# 16_Bit_Register.net
KiCad netlist of a schematic drawn in EAGLE
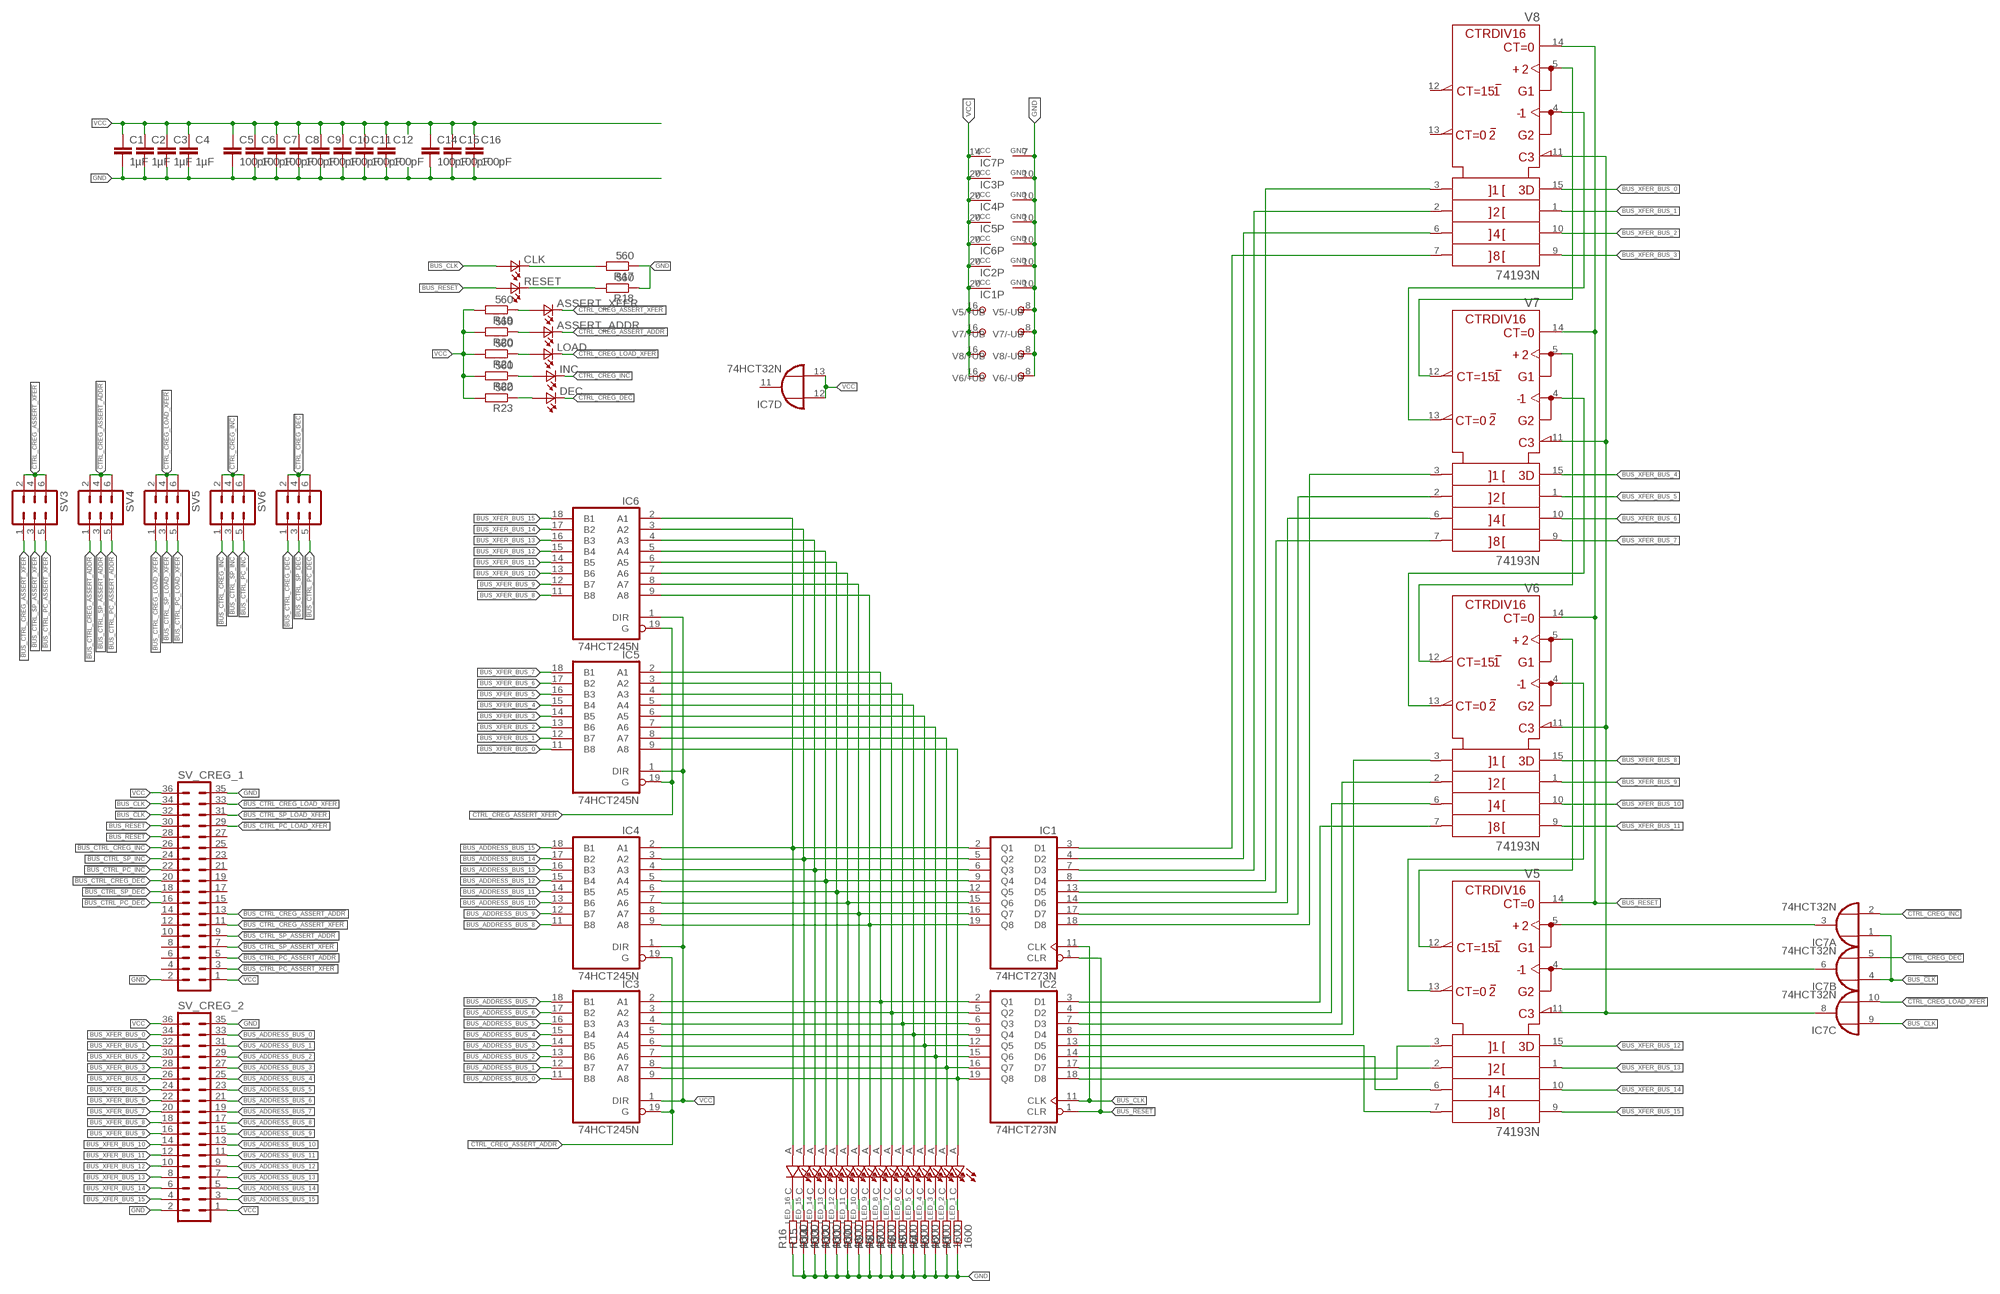
[diagram p0: schematic, sheet 1]

(export (version "E")
  (design (tool "Eeschema 10.0.6"))
  (components
    (comp (ref "ASSERT_ADDR")
      (value "LTST-C193TBKT-5A")
      (footprint "eagle-import:0603")
      (libsource (lib "eagle-import") (part "LTST-C193TBKT-5A"))
    )
    (comp (ref "ASSERT_XFER")
      (value "LTST-C193TBKT-5A")
      (footprint "eagle-import:0603")
      (libsource (lib "eagle-import") (part "LTST-C193TBKT-5A"))
    )
    (comp (ref "C1")
      (value "1µF")
      (footprint "eagle-import:C0805")
      (libsource (lib "eagle-import") (part "C-EUC0805"))
    )
    (comp (ref "C2")
      (value "1µF")
      (footprint "eagle-import:C0805")
      (libsource (lib "eagle-import") (part "C-EUC0805"))
    )
    (comp (ref "C3")
      (value "1µF")
      (footprint "eagle-import:C0805")
      (libsource (lib "eagle-import") (part "C-EUC0805"))
    )
    (comp (ref "C4")
      (value "1µF")
      (footprint "eagle-import:C0805")
      (libsource (lib "eagle-import") (part "C-EUC0805"))
    )
    (comp (ref "C5")
      (value "100pF")
      (footprint "eagle-import:C0805")
      (libsource (lib "eagle-import") (part "C-EUC0805"))
    )
    (comp (ref "C6")
      (value "100pF")
      (footprint "eagle-import:C0805")
      (libsource (lib "eagle-import") (part "C-EUC0805"))
    )
    (comp (ref "C7")
      (value "100pF")
      (footprint "eagle-import:C0805")
      (libsource (lib "eagle-import") (part "C-EUC0805"))
    )
    (comp (ref "C8")
      (value "100pF")
      (footprint "eagle-import:C0805")
      (libsource (lib "eagle-import") (part "C-EUC0805"))
    )
    (comp (ref "C9")
      (value "100pF")
      (footprint "eagle-import:C0805")
      (libsource (lib "eagle-import") (part "C-EUC0805"))
    )
    (comp (ref "C10")
      (value "100pF")
      (footprint "eagle-import:C0805")
      (libsource (lib "eagle-import") (part "C-EUC0805"))
    )
    (comp (ref "C11")
      (value "100pF")
      (footprint "eagle-import:C0805")
      (libsource (lib "eagle-import") (part "C-EUC0805"))
    )
    (comp (ref "C12")
      (value "100pF")
      (footprint "eagle-import:C0805")
      (libsource (lib "eagle-import") (part "C-EUC0805"))
    )
    (comp (ref "C14")
      (value "100pF")
      (footprint "eagle-import:C0805")
      (libsource (lib "eagle-import") (part "C-EUC0805"))
    )
    (comp (ref "C15")
      (value "100pF")
      (footprint "eagle-import:C0805")
      (libsource (lib "eagle-import") (part "C-EUC0805"))
    )
    (comp (ref "C16")
      (value "100pF")
      (footprint "eagle-import:C0805")
      (libsource (lib "eagle-import") (part "C-EUC0805"))
    )
    (comp (ref "CLK")
      (value "LTST-C193TBKT-5A")
      (footprint "eagle-import:0603")
      (libsource (lib "eagle-import") (part "LTST-C193TBKT-5A"))
    )
    (comp (ref "DEC")
      (value "LTST-C193TBKT-5A")
      (footprint "eagle-import:0603")
      (libsource (lib "eagle-import") (part "LTST-C193TBKT-5A"))
    )
    (comp (ref "IC1")
      (value "74HCT273N")
      (footprint "eagle-import:DIL20")
      (libsource (lib "eagle-import") (part "74273NHCT"))
    )
    (comp (ref "IC2")
      (value "74HCT273N")
      (footprint "eagle-import:DIL20")
      (libsource (lib "eagle-import") (part "74273NHCT"))
    )
    (comp (ref "IC3")
      (value "74HCT245N")
      (footprint "eagle-import:DIL20")
      (libsource (lib "eagle-import") (part "74245NHCT"))
    )
    (comp (ref "IC4")
      (value "74HCT245N")
      (footprint "eagle-import:DIL20")
      (libsource (lib "eagle-import") (part "74245NHCT"))
    )
    (comp (ref "IC5")
      (value "74HCT245N")
      (footprint "eagle-import:DIL20")
      (libsource (lib "eagle-import") (part "74245NHCT"))
    )
    (comp (ref "IC6")
      (value "74HCT245N")
      (footprint "eagle-import:DIL20")
      (libsource (lib "eagle-import") (part "74245NHCT"))
    )
    (comp (ref "IC7")
      (value "74HCT32N")
      (footprint "eagle-import:DIL14")
      (libsource (lib "eagle-import") (part "7432NHCT"))
    )
    (comp (ref "INC")
      (value "LTST-C193TBKT-5A")
      (footprint "eagle-import:0603")
      (libsource (lib "eagle-import") (part "LTST-C193TBKT-5A"))
    )
    (comp (ref "LED_1")
      (value "LTST-C193KRKT-5A")
      (footprint "eagle-import:LEDC1608X45N")
      (fields (field (name "MANUFACTURER") "Lite-On"))
      (libsource (lib "eagle-import") (part "LTST-C193KRKT-5A"))
    )
    (comp (ref "LED_2")
      (value "LTST-C193KRKT-5A")
      (footprint "eagle-import:LEDC1608X45N")
      (fields (field (name "MANUFACTURER") "Lite-On"))
      (libsource (lib "eagle-import") (part "LTST-C193KRKT-5A"))
    )
    (comp (ref "LED_3")
      (value "LTST-C193KRKT-5A")
      (footprint "eagle-import:LEDC1608X45N")
      (fields (field (name "MANUFACTURER") "Lite-On"))
      (libsource (lib "eagle-import") (part "LTST-C193KRKT-5A"))
    )
    (comp (ref "LED_4")
      (value "LTST-C193KRKT-5A")
      (footprint "eagle-import:LEDC1608X45N")
      (fields (field (name "MANUFACTURER") "Lite-On"))
      (libsource (lib "eagle-import") (part "LTST-C193KRKT-5A"))
    )
    (comp (ref "LED_5")
      (value "LTST-C193KRKT-5A")
      (footprint "eagle-import:LEDC1608X45N")
      (fields (field (name "MANUFACTURER") "Lite-On"))
      (libsource (lib "eagle-import") (part "LTST-C193KRKT-5A"))
    )
    (comp (ref "LED_6")
      (value "LTST-C193KRKT-5A")
      (footprint "eagle-import:LEDC1608X45N")
      (fields (field (name "MANUFACTURER") "Lite-On"))
      (libsource (lib "eagle-import") (part "LTST-C193KRKT-5A"))
    )
    (comp (ref "LED_7")
      (value "LTST-C193KRKT-5A")
      (footprint "eagle-import:LEDC1608X45N")
      (fields (field (name "MANUFACTURER") "Lite-On"))
      (libsource (lib "eagle-import") (part "LTST-C193KRKT-5A"))
    )
    (comp (ref "LED_8")
      (value "LTST-C193KRKT-5A")
      (footprint "eagle-import:LEDC1608X45N")
      (fields (field (name "MANUFACTURER") "Lite-On"))
      (libsource (lib "eagle-import") (part "LTST-C193KRKT-5A"))
    )
    (comp (ref "LED_9")
      (value "LTST-C193KRKT-5A")
      (footprint "eagle-import:LEDC1608X45N")
      (fields (field (name "MANUFACTURER") "Lite-On"))
      (libsource (lib "eagle-import") (part "LTST-C193KRKT-5A"))
    )
    (comp (ref "LED_10")
      (value "LTST-C193KRKT-5A")
      (footprint "eagle-import:LEDC1608X45N")
      (fields (field (name "MANUFACTURER") "Lite-On"))
      (libsource (lib "eagle-import") (part "LTST-C193KRKT-5A"))
    )
    (comp (ref "LED_11")
      (value "LTST-C193KRKT-5A")
      (footprint "eagle-import:LEDC1608X45N")
      (fields (field (name "MANUFACTURER") "Lite-On"))
      (libsource (lib "eagle-import") (part "LTST-C193KRKT-5A"))
    )
    (comp (ref "LED_12")
      (value "LTST-C193KRKT-5A")
      (footprint "eagle-import:LEDC1608X45N")
      (fields (field (name "MANUFACTURER") "Lite-On"))
      (libsource (lib "eagle-import") (part "LTST-C193KRKT-5A"))
    )
    (comp (ref "LED_13")
      (value "LTST-C193KRKT-5A")
      (footprint "eagle-import:LEDC1608X45N")
      (fields (field (name "MANUFACTURER") "Lite-On"))
      (libsource (lib "eagle-import") (part "LTST-C193KRKT-5A"))
    )
    (comp (ref "LED_14")
      (value "LTST-C193KRKT-5A")
      (footprint "eagle-import:LEDC1608X45N")
      (fields (field (name "MANUFACTURER") "Lite-On"))
      (libsource (lib "eagle-import") (part "LTST-C193KRKT-5A"))
    )
    (comp (ref "LED_15")
      (value "LTST-C193KRKT-5A")
      (footprint "eagle-import:LEDC1608X45N")
      (fields (field (name "MANUFACTURER") "Lite-On"))
      (libsource (lib "eagle-import") (part "LTST-C193KRKT-5A"))
    )
    (comp (ref "LED_16")
      (value "LTST-C193KRKT-5A")
      (footprint "eagle-import:LEDC1608X45N")
      (fields (field (name "MANUFACTURER") "Lite-On"))
      (libsource (lib "eagle-import") (part "LTST-C193KRKT-5A"))
    )
    (comp (ref "LOAD")
      (value "LTST-C193TBKT-5A")
      (footprint "eagle-import:0603")
      (libsource (lib "eagle-import") (part "LTST-C193TBKT-5A"))
    )
    (comp (ref "R1")
      (value "1600")
      (footprint "eagle-import:R0805")
      (libsource (lib "eagle-import") (part "R-EU_R0805"))
    )
    (comp (ref "R2")
      (value "1600")
      (footprint "eagle-import:R0805")
      (libsource (lib "eagle-import") (part "R-EU_R0805"))
    )
    (comp (ref "R3")
      (value "1600")
      (footprint "eagle-import:R0805")
      (libsource (lib "eagle-import") (part "R-EU_R0805"))
    )
    (comp (ref "R4")
      (value "1600")
      (footprint "eagle-import:R0805")
      (libsource (lib "eagle-import") (part "R-EU_R0805"))
    )
    (comp (ref "R5")
      (value "1600")
      (footprint "eagle-import:R0805")
      (libsource (lib "eagle-import") (part "R-EU_R0805"))
    )
    (comp (ref "R6")
      (value "1600")
      (footprint "eagle-import:R0805")
      (libsource (lib "eagle-import") (part "R-EU_R0805"))
    )
    (comp (ref "R7")
      (value "1600")
      (footprint "eagle-import:R0805")
      (libsource (lib "eagle-import") (part "R-EU_R0805"))
    )
    (comp (ref "R8")
      (value "1600")
      (footprint "eagle-import:R0805")
      (libsource (lib "eagle-import") (part "R-EU_R0805"))
    )
    (comp (ref "R9")
      (value "1600")
      (footprint "eagle-import:R0805")
      (libsource (lib "eagle-import") (part "R-EU_R0805"))
    )
    (comp (ref "R10")
      (value "1600")
      (footprint "eagle-import:R0805")
      (libsource (lib "eagle-import") (part "R-EU_R0805"))
    )
    (comp (ref "R11")
      (value "1600")
      (footprint "eagle-import:R0805")
      (libsource (lib "eagle-import") (part "R-EU_R0805"))
    )
    (comp (ref "R12")
      (value "1600")
      (footprint "eagle-import:R0805")
      (libsource (lib "eagle-import") (part "R-EU_R0805"))
    )
    (comp (ref "R13")
      (value "1600")
      (footprint "eagle-import:R0805")
      (libsource (lib "eagle-import") (part "R-EU_R0805"))
    )
    (comp (ref "R14")
      (value "1600")
      (footprint "eagle-import:R0805")
      (libsource (lib "eagle-import") (part "R-EU_R0805"))
    )
    (comp (ref "R15")
      (value "1600")
      (footprint "eagle-import:R0805")
      (libsource (lib "eagle-import") (part "R-EU_R0805"))
    )
    (comp (ref "R16")
      (value "1600")
      (footprint "eagle-import:R0805")
      (libsource (lib "eagle-import") (part "R-EU_R0805"))
    )
    (comp (ref "R17")
      (value "560")
      (footprint "eagle-import:R0805")
      (libsource (lib "eagle-import") (part "R-EU_R0805"))
    )
    (comp (ref "R18")
      (value "560")
      (footprint "eagle-import:R0805")
      (libsource (lib "eagle-import") (part "R-EU_R0805"))
    )
    (comp (ref "R19")
      (value "560")
      (footprint "eagle-import:R0805")
      (libsource (lib "eagle-import") (part "R-EU_R0805"))
    )
    (comp (ref "R20")
      (value "560")
      (footprint "eagle-import:R0805")
      (libsource (lib "eagle-import") (part "R-EU_R0805"))
    )
    (comp (ref "R21")
      (value "560")
      (footprint "eagle-import:R0805")
      (libsource (lib "eagle-import") (part "R-EU_R0805"))
    )
    (comp (ref "R22")
      (value "560")
      (footprint "eagle-import:R0805")
      (libsource (lib "eagle-import") (part "R-EU_R0805"))
    )
    (comp (ref "R23")
      (value "560")
      (footprint "eagle-import:R0805")
      (libsource (lib "eagle-import") (part "R-EU_R0805"))
    )
    (comp (ref "RESET")
      (value "LTST-C193TBKT-5A")
      (footprint "eagle-import:0603")
      (libsource (lib "eagle-import") (part "LTST-C193TBKT-5A"))
    )
    (comp (ref "SV3")
      (value "MA03-2")
      (footprint "eagle-import:MA03-2")
      (libsource (lib "eagle-import") (part "MA03-2"))
    )
    (comp (ref "SV4")
      (value "MA03-2")
      (footprint "eagle-import:MA03-2")
      (libsource (lib "eagle-import") (part "MA03-2"))
    )
    (comp (ref "SV5")
      (value "MA03-2")
      (footprint "eagle-import:MA03-2")
      (libsource (lib "eagle-import") (part "MA03-2"))
    )
    (comp (ref "SV6")
      (value "MA03-2")
      (footprint "eagle-import:MA03-2")
      (libsource (lib "eagle-import") (part "MA03-2"))
    )
    (comp (ref "SV7")
      (value "MA03-2")
      (footprint "eagle-import:MA03-2")
      (libsource (lib "eagle-import") (part "MA03-2"))
    )
    (comp (ref "SV_CREG_1")
      (value "MA18-2")
      (footprint "eagle-import:MA18-2")
      (libsource (lib "eagle-import") (part "MA18-2"))
    )
    (comp (ref "SV_CREG_2")
      (value "MA18-2")
      (footprint "eagle-import:MA18-2")
      (libsource (lib "eagle-import") (part "MA18-2"))
    )
    (comp (ref "V5")
      (value "74193N")
      (footprint "eagle-import:DIL16")
      (libsource (lib "eagle-import") (part "74193N"))
    )
    (comp (ref "V6")
      (value "74193N")
      (footprint "eagle-import:DIL16")
      (libsource (lib "eagle-import") (part "74193N"))
    )
    (comp (ref "V7")
      (value "74193N")
      (footprint "eagle-import:DIL16")
      (libsource (lib "eagle-import") (part "74193N"))
    )
    (comp (ref "V8")
      (value "74193N")
      (footprint "eagle-import:DIL16")
      (libsource (lib "eagle-import") (part "74193N"))
    )
  )
  (nets
    (net (code "1") (name "/BUS_~{CLK}") (class "Default")
      (node (ref "IC7") (pin "1") (pinfunction "I0_1") (pintype "input"))
      (node (ref "IC7") (pin "4") (pinfunction "I0_4") (pintype "input"))
      (node (ref "SV_CREG_1") (pin "32") (pinfunction "32_32") (pintype "passive"))
    )
    (net (code "2") (name "/BUS_~{RESET}") (class "Default")
      (node (ref "IC1") (pin "1") (pinfunction "CLR_1") (pintype "input"))
      (node (ref "IC2") (pin "1") (pinfunction "CLR_1") (pintype "input"))
      (node (ref "SV_CREG_1") (pin "28") (pinfunction "28_28") (pintype "passive"))
    )
    (net (code "3") (name "/~{BUS_CTRL_CREG_ASSERT_ADDR}") (class "Default")
      (node (ref "SV4") (pin "1") (pinfunction "1_1") (pintype "passive"))
      (node (ref "SV_CREG_1") (pin "13") (pinfunction "13_13") (pintype "passive"))
    )
    (net (code "4") (name "/~{BUS_CTRL_CREG_ASSERT_XFER}") (class "Default")
      (node (ref "SV3") (pin "1") (pinfunction "1_1") (pintype "passive"))
      (node (ref "SV_CREG_1") (pin "11") (pinfunction "11_11") (pintype "passive"))
    )
    (net (code "5") (name "/~{BUS_CTRL_CREG_DEC}") (class "Default")
      (node (ref "SV7") (pin "1") (pinfunction "1_1") (pintype "passive"))
      (node (ref "SV_CREG_1") (pin "20") (pinfunction "20_20") (pintype "passive"))
    )
    (net (code "6") (name "/~{BUS_CTRL_CREG_INC}") (class "Default")
      (node (ref "SV6") (pin "1") (pinfunction "1_1") (pintype "passive"))
      (node (ref "SV_CREG_1") (pin "26") (pinfunction "26_26") (pintype "passive"))
    )
    (net (code "7") (name "/~{BUS_CTRL_CREG_LOAD_XFER}") (class "Default")
      (node (ref "SV5") (pin "1") (pinfunction "1_1") (pintype "passive"))
      (node (ref "SV_CREG_1") (pin "33") (pinfunction "33_33") (pintype "passive"))
    )
    (net (code "8") (name "/~{BUS_CTRL_PC_ASSERT_ADDR}") (class "Default")
      (node (ref "SV4") (pin "5") (pinfunction "5_5") (pintype "passive"))
      (node (ref "SV_CREG_1") (pin "5") (pinfunction "5_5") (pintype "passive"))
    )
    (net (code "9") (name "/~{BUS_CTRL_PC_ASSERT_XFER}") (class "Default")
      (node (ref "SV3") (pin "5") (pinfunction "5_5") (pintype "passive"))
      (node (ref "SV_CREG_1") (pin "3") (pinfunction "3_3") (pintype "passive"))
    )
    (net (code "10") (name "/~{BUS_CTRL_PC_DEC}") (class "Default")
      (node (ref "SV7") (pin "5") (pinfunction "5_5") (pintype "passive"))
      (node (ref "SV_CREG_1") (pin "16") (pinfunction "16_16") (pintype "passive"))
    )
    (net (code "11") (name "/~{BUS_CTRL_PC_INC}") (class "Default")
      (node (ref "SV6") (pin "5") (pinfunction "5_5") (pintype "passive"))
      (node (ref "SV_CREG_1") (pin "22") (pinfunction "22_22") (pintype "passive"))
    )
    (net (code "12") (name "/~{BUS_CTRL_PC_LOAD_XFER}") (class "Default")
      (node (ref "SV5") (pin "5") (pinfunction "5_5") (pintype "passive"))
      (node (ref "SV_CREG_1") (pin "29") (pinfunction "29_29") (pintype "passive"))
    )
    (net (code "13") (name "/~{BUS_CTRL_SP_ASSERT_ADDR}") (class "Default")
      (node (ref "SV4") (pin "3") (pinfunction "3_3") (pintype "passive"))
      (node (ref "SV_CREG_1") (pin "9") (pinfunction "9_9") (pintype "passive"))
    )
    (net (code "14") (name "/~{BUS_CTRL_SP_ASSERT_XFER}") (class "Default")
      (node (ref "SV3") (pin "3") (pinfunction "3_3") (pintype "passive"))
      (node (ref "SV_CREG_1") (pin "7") (pinfunction "7_7") (pintype "passive"))
    )
    (net (code "15") (name "/~{BUS_CTRL_SP_DEC}") (class "Default")
      (node (ref "SV7") (pin "3") (pinfunction "3_3") (pintype "passive"))
      (node (ref "SV_CREG_1") (pin "18") (pinfunction "18_18") (pintype "passive"))
    )
    (net (code "16") (name "/~{BUS_CTRL_SP_INC}") (class "Default")
      (node (ref "SV6") (pin "3") (pinfunction "3_3") (pintype "passive"))
      (node (ref "SV_CREG_1") (pin "24") (pinfunction "24_24") (pintype "passive"))
    )
    (net (code "17") (name "/~{BUS_CTRL_SP_LOAD_XFER}") (class "Default")
      (node (ref "SV5") (pin "3") (pinfunction "3_3") (pintype "passive"))
      (node (ref "SV_CREG_1") (pin "31") (pinfunction "31_31") (pintype "passive"))
    )
    (net (code "18") (name "/~{CTRL_CREG_ASSERT_ADDR}") (class "Default")
      (node (ref "ASSERT_ADDR") (pin "1") (pinfunction "K2_1") (pintype "passive"))
      (node (ref "IC3") (pin "19") (pinfunction "G_19") (pintype "input"))
      (node (ref "IC4") (pin "19") (pinfunction "G_19") (pintype "input"))
      (node (ref "SV4") (pin "2") (pinfunction "2_2") (pintype "passive"))
      (node (ref "SV4") (pin "4") (pinfunction "4_4") (pintype "passive"))
      (node (ref "SV4") (pin "6") (pinfunction "6_6") (pintype "passive"))
    )
    (net (code "19") (name "/~{CTRL_CREG_ASSERT_XFER}") (class "Default")
      (node (ref "ASSERT_XFER") (pin "1") (pinfunction "K2_1") (pintype "passive"))
      (node (ref "IC5") (pin "19") (pinfunction "G_19") (pintype "input"))
      (node (ref "IC6") (pin "19") (pinfunction "G_19") (pintype "input"))
      (node (ref "SV3") (pin "2") (pinfunction "2_2") (pintype "passive"))
      (node (ref "SV3") (pin "4") (pinfunction "4_4") (pintype "passive"))
      (node (ref "SV3") (pin "6") (pinfunction "6_6") (pintype "passive"))
    )
    (net (code "20") (name "/~{CTRL_CREG_DEC}") (class "Default")
      (node (ref "DEC") (pin "1") (pinfunction "K2_1") (pintype "passive"))
      (node (ref "IC7") (pin "5") (pinfunction "I1_5") (pintype "input"))
      (node (ref "SV7") (pin "2") (pinfunction "2_2") (pintype "passive"))
      (node (ref "SV7") (pin "4") (pinfunction "4_4") (pintype "passive"))
      (node (ref "SV7") (pin "6") (pinfunction "6_6") (pintype "passive"))
    )
    (net (code "21") (name "/~{CTRL_CREG_INC}") (class "Default")
      (node (ref "IC7") (pin "2") (pinfunction "I1_2") (pintype "input"))
      (node (ref "INC") (pin "1") (pinfunction "K2_1") (pintype "passive"))
      (node (ref "SV6") (pin "2") (pinfunction "2_2") (pintype "passive"))
      (node (ref "SV6") (pin "4") (pinfunction "4_4") (pintype "passive"))
      (node (ref "SV6") (pin "6") (pinfunction "6_6") (pintype "passive"))
    )
    (net (code "22") (name "/~{CTRL_CREG_LOAD_XFER}") (class "Default")
      (node (ref "IC7") (pin "10") (pinfunction "I1_10") (pintype "input"))
      (node (ref "LOAD") (pin "1") (pinfunction "K2_1") (pintype "passive"))
      (node (ref "SV5") (pin "2") (pinfunction "2_2") (pintype "passive"))
      (node (ref "SV5") (pin "4") (pinfunction "4_4") (pintype "passive"))
      (node (ref "SV5") (pin "6") (pinfunction "6_6") (pintype "passive"))
    )
    (net (code "23") (name "BUS_ADDRESS_BUS_0") (class "Default")
      (node (ref "IC3") (pin "11") (pinfunction "B8_11") (pintype "bidirectional"))
      (node (ref "SV_CREG_2") (pin "33") (pinfunction "33_33") (pintype "passive"))
    )
    (net (code "24") (name "BUS_ADDRESS_BUS_1") (class "Default")
      (node (ref "IC3") (pin "12") (pinfunction "B7_12") (pintype "bidirectional"))
      (node (ref "SV_CREG_2") (pin "31") (pinfunction "31_31") (pintype "passive"))
    )
    (net (code "25") (name "BUS_ADDRESS_BUS_2") (class "Default")
      (node (ref "IC3") (pin "13") (pinfunction "B6_13") (pintype "bidirectional"))
      (node (ref "SV_CREG_2") (pin "29") (pinfunction "29_29") (pintype "passive"))
    )
    (net (code "26") (name "BUS_ADDRESS_BUS_3") (class "Default")
      (node (ref "IC3") (pin "14") (pinfunction "B5_14") (pintype "bidirectional"))
      (node (ref "SV_CREG_2") (pin "27") (pinfunction "27_27") (pintype "passive"))
    )
    (net (code "27") (name "BUS_ADDRESS_BUS_4") (class "Default")
      (node (ref "IC3") (pin "15") (pinfunction "B4_15") (pintype "bidirectional"))
      (node (ref "SV_CREG_2") (pin "25") (pinfunction "25_25") (pintype "passive"))
    )
    (net (code "28") (name "BUS_ADDRESS_BUS_5") (class "Default")
      (node (ref "IC3") (pin "16") (pinfunction "B3_16") (pintype "bidirectional"))
      (node (ref "SV_CREG_2") (pin "23") (pinfunction "23_23") (pintype "passive"))
    )
    (net (code "29") (name "BUS_ADDRESS_BUS_6") (class "Default")
      (node (ref "IC3") (pin "17") (pinfunction "B2_17") (pintype "bidirectional"))
      (node (ref "SV_CREG_2") (pin "21") (pinfunction "21_21") (pintype "passive"))
    )
    (net (code "30") (name "BUS_ADDRESS_BUS_7") (class "Default")
      (node (ref "IC3") (pin "18") (pinfunction "B1_18") (pintype "bidirectional"))
      (node (ref "SV_CREG_2") (pin "19") (pinfunction "19_19") (pintype "passive"))
    )
    (net (code "31") (name "BUS_ADDRESS_BUS_8") (class "Default")
      (node (ref "IC4") (pin "11") (pinfunction "B8_11") (pintype "bidirectional"))
      (node (ref "SV_CREG_2") (pin "17") (pinfunction "17_17") (pintype "passive"))
    )
    (net (code "32") (name "BUS_ADDRESS_BUS_9") (class "Default")
      (node (ref "IC4") (pin "12") (pinfunction "B7_12") (pintype "bidirectional"))
      (node (ref "SV_CREG_2") (pin "15") (pinfunction "15_15") (pintype "passive"))
    )
    (net (code "33") (name "BUS_ADDRESS_BUS_10") (class "Default")
      (node (ref "IC4") (pin "13") (pinfunction "B6_13") (pintype "bidirectional"))
      (node (ref "SV_CREG_2") (pin "13") (pinfunction "13_13") (pintype "passive"))
    )
    (net (code "34") (name "BUS_ADDRESS_BUS_11") (class "Default")
      (node (ref "IC4") (pin "14") (pinfunction "B5_14") (pintype "bidirectional"))
      (node (ref "SV_CREG_2") (pin "11") (pinfunction "11_11") (pintype "passive"))
    )
    (net (code "35") (name "BUS_ADDRESS_BUS_12") (class "Default")
      (node (ref "IC4") (pin "15") (pinfunction "B4_15") (pintype "bidirectional"))
      (node (ref "SV_CREG_2") (pin "9") (pinfunction "9_9") (pintype "passive"))
    )
    (net (code "36") (name "BUS_ADDRESS_BUS_13") (class "Default")
      (node (ref "IC4") (pin "16") (pinfunction "B3_16") (pintype "bidirectional"))
      (node (ref "SV_CREG_2") (pin "7") (pinfunction "7_7") (pintype "passive"))
    )
    (net (code "37") (name "BUS_ADDRESS_BUS_14") (class "Default")
      (node (ref "IC4") (pin "17") (pinfunction "B2_17") (pintype "bidirectional"))
      (node (ref "SV_CREG_2") (pin "5") (pinfunction "5_5") (pintype "passive"))
    )
    (net (code "38") (name "BUS_ADDRESS_BUS_15") (class "Default")
      (node (ref "IC4") (pin "18") (pinfunction "B1_18") (pintype "bidirectional"))
      (node (ref "SV_CREG_2") (pin "3") (pinfunction "3_3") (pintype "passive"))
    )
    (net (code "39") (name "BUS_CLK") (class "Default")
      (node (ref "CLK") (pin "2") (pinfunction "A2_2") (pintype "passive"))
      (node (ref "IC1") (pin "11") (pinfunction "CLK_11") (pintype "input"))
      (node (ref "IC2") (pin "11") (pinfunction "CLK_11") (pintype "input"))
      (node (ref "IC7") (pin "9") (pinfunction "I0_9") (pintype "input"))
      (node (ref "SV_CREG_1") (pin "34") (pinfunction "34_34") (pintype "passive"))
    )
    (net (code "40") (name "BUS_RESET") (class "Default")
      (node (ref "RESET") (pin "2") (pinfunction "A2_2") (pintype "passive"))
      (node (ref "SV_CREG_1") (pin "30") (pinfunction "30_30") (pintype "passive"))
      (node (ref "V5") (pin "14") (pinfunction "CLR_14") (pintype "input"))
      (node (ref "V6") (pin "14") (pinfunction "CLR_14") (pintype "input"))
      (node (ref "V7") (pin "14") (pinfunction "CLR_14") (pintype "input"))
      (node (ref "V8") (pin "14") (pinfunction "CLR_14") (pintype "input"))
    )
    (net (code "41") (name "BUS_XFER_BUS_0") (class "Default")
      (node (ref "IC5") (pin "11") (pinfunction "B8_11") (pintype "bidirectional"))
      (node (ref "SV_CREG_2") (pin "34") (pinfunction "34_34") (pintype "passive"))
      (node (ref "V8") (pin "15") (pinfunction "A_15") (pintype "input"))
    )
    (net (code "42") (name "BUS_XFER_BUS_1") (class "Default")
      (node (ref "IC5") (pin "12") (pinfunction "B7_12") (pintype "bidirectional"))
      (node (ref "SV_CREG_2") (pin "32") (pinfunction "32_32") (pintype "passive"))
      (node (ref "V8") (pin "1") (pinfunction "B_1") (pintype "input"))
    )
    (net (code "43") (name "BUS_XFER_BUS_2") (class "Default")
      (node (ref "IC5") (pin "13") (pinfunction "B6_13") (pintype "bidirectional"))
      (node (ref "SV_CREG_2") (pin "30") (pinfunction "30_30") (pintype "passive"))
      (node (ref "V8") (pin "10") (pinfunction "C_10") (pintype "input"))
    )
    (net (code "44") (name "BUS_XFER_BUS_3") (class "Default")
      (node (ref "IC5") (pin "14") (pinfunction "B5_14") (pintype "bidirectional"))
      (node (ref "SV_CREG_2") (pin "28") (pinfunction "28_28") (pintype "passive"))
      (node (ref "V8") (pin "9") (pinfunction "D_9") (pintype "input"))
    )
    (net (code "45") (name "BUS_XFER_BUS_4") (class "Default")
      (node (ref "IC5") (pin "15") (pinfunction "B4_15") (pintype "bidirectional"))
      (node (ref "SV_CREG_2") (pin "26") (pinfunction "26_26") (pintype "passive"))
      (node (ref "V7") (pin "15") (pinfunction "A_15") (pintype "input"))
    )
    (net (code "46") (name "BUS_XFER_BUS_5") (class "Default")
      (node (ref "IC5") (pin "16") (pinfunction "B3_16") (pintype "bidirectional"))
      (node (ref "SV_CREG_2") (pin "24") (pinfunction "24_24") (pintype "passive"))
      (node (ref "V7") (pin "1") (pinfunction "B_1") (pintype "input"))
    )
    (net (code "47") (name "BUS_XFER_BUS_6") (class "Default")
      (node (ref "IC5") (pin "17") (pinfunction "B2_17") (pintype "bidirectional"))
      (node (ref "SV_CREG_2") (pin "22") (pinfunction "22_22") (pintype "passive"))
      (node (ref "V7") (pin "10") (pinfunction "C_10") (pintype "input"))
    )
    (net (code "48") (name "BUS_XFER_BUS_7") (class "Default")
      (node (ref "IC5") (pin "18") (pinfunction "B1_18") (pintype "bidirectional"))
      (node (ref "SV_CREG_2") (pin "20") (pinfunction "20_20") (pintype "passive"))
      (node (ref "V7") (pin "9") (pinfunction "D_9") (pintype "input"))
    )
    (net (code "49") (name "BUS_XFER_BUS_8") (class "Default")
      (node (ref "IC6") (pin "11") (pinfunction "B8_11") (pintype "bidirectional"))
      (node (ref "SV_CREG_2") (pin "18") (pinfunction "18_18") (pintype "passive"))
      (node (ref "V6") (pin "15") (pinfunction "A_15") (pintype "input"))
    )
    (net (code "50") (name "BUS_XFER_BUS_9") (class "Default")
      (node (ref "IC6") (pin "12") (pinfunction "B7_12") (pintype "bidirectional"))
      (node (ref "SV_CREG_2") (pin "16") (pinfunction "16_16") (pintype "passive"))
      (node (ref "V6") (pin "1") (pinfunction "B_1") (pintype "input"))
    )
    (net (code "51") (name "BUS_XFER_BUS_10") (class "Default")
      (node (ref "IC6") (pin "13") (pinfunction "B6_13") (pintype "bidirectional"))
      (node (ref "SV_CREG_2") (pin "14") (pinfunction "14_14") (pintype "passive"))
      (node (ref "V6") (pin "10") (pinfunction "C_10") (pintype "input"))
    )
    (net (code "52") (name "BUS_XFER_BUS_11") (class "Default")
      (node (ref "IC6") (pin "14") (pinfunction "B5_14") (pintype "bidirectional"))
      (node (ref "SV_CREG_2") (pin "12") (pinfunction "12_12") (pintype "passive"))
      (node (ref "V6") (pin "9") (pinfunction "D_9") (pintype "input"))
    )
    (net (code "53") (name "BUS_XFER_BUS_12") (class "Default")
      (node (ref "IC6") (pin "15") (pinfunction "B4_15") (pintype "bidirectional"))
      (node (ref "SV_CREG_2") (pin "10") (pinfunction "10_10") (pintype "passive"))
      (node (ref "V5") (pin "15") (pinfunction "A_15") (pintype "input"))
    )
    (net (code "54") (name "BUS_XFER_BUS_13") (class "Default")
      (node (ref "IC6") (pin "16") (pinfunction "B3_16") (pintype "bidirectional"))
      (node (ref "SV_CREG_2") (pin "8") (pinfunction "8_8") (pintype "passive"))
      (node (ref "V5") (pin "1") (pinfunction "B_1") (pintype "input"))
    )
    (net (code "55") (name "BUS_XFER_BUS_14") (class "Default")
      (node (ref "IC6") (pin "17") (pinfunction "B2_17") (pintype "bidirectional"))
      (node (ref "SV_CREG_2") (pin "6") (pinfunction "6_6") (pintype "passive"))
      (node (ref "V5") (pin "10") (pinfunction "C_10") (pintype "input"))
    )
    (net (code "56") (name "BUS_XFER_BUS_15") (class "Default")
      (node (ref "IC6") (pin "18") (pinfunction "B1_18") (pintype "bidirectional"))
      (node (ref "SV_CREG_2") (pin "4") (pinfunction "4_4") (pintype "passive"))
      (node (ref "V5") (pin "9") (pinfunction "D_9") (pintype "input"))
    )
    (net (code "57") (name "GND") (class "Default")
      (node (ref "C1") (pin "2") (pinfunction "2_2") (pintype "passive"))
      (node (ref "C10") (pin "2") (pinfunction "2_2") (pintype "passive"))
      (node (ref "C11") (pin "2") (pinfunction "2_2") (pintype "passive"))
      (node (ref "C12") (pin "2") (pinfunction "2_2") (pintype "passive"))
      (node (ref "C14") (pin "2") (pinfunction "2_2") (pintype "passive"))
      (node (ref "C15") (pin "2") (pinfunction "2_2") (pintype "passive"))
      (node (ref "C16") (pin "2") (pinfunction "2_2") (pintype "passive"))
      (node (ref "C2") (pin "2") (pinfunction "2_2") (pintype "passive"))
      (node (ref "C3") (pin "2") (pinfunction "2_2") (pintype "passive"))
      (node (ref "C4") (pin "2") (pinfunction "2_2") (pintype "passive"))
      (node (ref "C5") (pin "2") (pinfunction "2_2") (pintype "passive"))
      (node (ref "C6") (pin "2") (pinfunction "2_2") (pintype "passive"))
      (node (ref "C7") (pin "2") (pinfunction "2_2") (pintype "passive"))
      (node (ref "C8") (pin "2") (pinfunction "2_2") (pintype "passive"))
      (node (ref "C9") (pin "2") (pinfunction "2_2") (pintype "passive"))
      (node (ref "IC1") (pin "10") (pinfunction "GND_10") (pintype "power_in"))
      (node (ref "IC2") (pin "10") (pinfunction "GND_10") (pintype "power_in"))
      (node (ref "IC3") (pin "10") (pinfunction "GND_10") (pintype "power_in"))
      (node (ref "IC4") (pin "10") (pinfunction "GND_10") (pintype "power_in"))
      (node (ref "IC5") (pin "10") (pinfunction "GND_10") (pintype "power_in"))
      (node (ref "IC6") (pin "10") (pinfunction "GND_10") (pintype "power_in"))
      (node (ref "IC7") (pin "7") (pinfunction "GND_7") (pintype "power_in"))
      (node (ref "R1") (pin "1") (pinfunction "1_1") (pintype "passive"))
      (node (ref "R10") (pin "1") (pinfunction "1_1") (pintype "passive"))
      (node (ref "R11") (pin "1") (pinfunction "1_1") (pintype "passive"))
      (node (ref "R12") (pin "1") (pinfunction "1_1") (pintype "passive"))
      (node (ref "R13") (pin "1") (pinfunction "1_1") (pintype "passive"))
      (node (ref "R14") (pin "1") (pinfunction "1_1") (pintype "passive"))
      (node (ref "R15") (pin "1") (pinfunction "1_1") (pintype "passive"))
      (node (ref "R16") (pin "1") (pinfunction "1_1") (pintype "passive"))
      (node (ref "R17") (pin "1") (pinfunction "1_1") (pintype "passive"))
      (node (ref "R18") (pin "1") (pinfunction "1_1") (pintype "passive"))
      (node (ref "R2") (pin "1") (pinfunction "1_1") (pintype "passive"))
      (node (ref "R3") (pin "1") (pinfunction "1_1") (pintype "passive"))
      (node (ref "R4") (pin "1") (pinfunction "1_1") (pintype "passive"))
      (node (ref "R5") (pin "1") (pinfunction "1_1") (pintype "passive"))
      (node (ref "R6") (pin "1") (pinfunction "1_1") (pintype "passive"))
      (node (ref "R7") (pin "1") (pinfunction "1_1") (pintype "passive"))
      (node (ref "R8") (pin "1") (pinfunction "1_1") (pintype "passive"))
      (node (ref "R9") (pin "1") (pinfunction "1_1") (pintype "passive"))
      (node (ref "SV_CREG_1") (pin "2") (pinfunction "2_2") (pintype "passive"))
      (node (ref "SV_CREG_1") (pin "35") (pinfunction "35_35") (pintype "passive"))
      (node (ref "SV_CREG_2") (pin "2") (pinfunction "2_2") (pintype "passive"))
      (node (ref "SV_CREG_2") (pin "35") (pinfunction "35_35") (pintype "passive"))
      (node (ref "V5") (pin "8") (pinfunction "-UB_8") (pintype "power_in"))
      (node (ref "V6") (pin "8") (pinfunction "-UB_8") (pintype "power_in"))
      (node (ref "V7") (pin "8") (pinfunction "-UB_8") (pintype "power_in"))
      (node (ref "V8") (pin "8") (pinfunction "-UB_8") (pintype "power_in"))
    )
    (net (code "58") (name "Net-(ASSERT_ADDR-A2)") (class "Default")
      (node (ref "ASSERT_ADDR") (pin "2") (pinfunction "A2_2") (pintype "passive"))
      (node (ref "R20") (pin "1") (pinfunction "1_1") (pintype "passive"))
    )
    (net (code "59") (name "Net-(ASSERT_XFER-A2)") (class "Default")
      (node (ref "ASSERT_XFER") (pin "2") (pinfunction "A2_2") (pintype "passive"))
      (node (ref "R19") (pin "1") (pinfunction "1_1") (pintype "passive"))
    )
    (net (code "60") (name "Net-(CLK-K2)") (class "Default")
      (node (ref "CLK") (pin "1") (pinfunction "K2_1") (pintype "passive"))
      (node (ref "R17") (pin "2") (pinfunction "2_2") (pintype "passive"))
    )
    (net (code "61") (name "Net-(DEC-A2)") (class "Default")
      (node (ref "DEC") (pin "2") (pinfunction "A2_2") (pintype "passive"))
      (node (ref "R23") (pin "1") (pinfunction "1_1") (pintype "passive"))
    )
    (net (code "62") (name "Net-(IC1A-D1)") (class "Default")
      (node (ref "IC1") (pin "3") (pinfunction "D1_3") (pintype "input"))
      (node (ref "V8") (pin "7") (pinfunction "QD_7") (pintype "output"))
    )
    (net (code "63") (name "Net-(IC1A-D2)") (class "Default")
      (node (ref "IC1") (pin "4") (pinfunction "D2_4") (pintype "input"))
      (node (ref "V8") (pin "6") (pinfunction "QC_6") (pintype "output"))
    )
    (net (code "64") (name "Net-(IC1A-D3)") (class "Default")
      (node (ref "IC1") (pin "7") (pinfunction "D3_7") (pintype "input"))
      (node (ref "V8") (pin "2") (pinfunction "QB_2") (pintype "output"))
    )
    (net (code "65") (name "Net-(IC1A-D4)") (class "Default")
      (node (ref "IC1") (pin "8") (pinfunction "D4_8") (pintype "input"))
      (node (ref "V8") (pin "3") (pinfunction "QA_3") (pintype "output"))
    )
    (net (code "66") (name "Net-(IC1A-D5)") (class "Default")
      (node (ref "IC1") (pin "13") (pinfunction "D5_13") (pintype "input"))
      (node (ref "V7") (pin "7") (pinfunction "QD_7") (pintype "output"))
    )
    (net (code "67") (name "Net-(IC1A-D6)") (class "Default")
      (node (ref "IC1") (pin "14") (pinfunction "D6_14") (pintype "input"))
      (node (ref "V7") (pin "6") (pinfunction "QC_6") (pintype "output"))
    )
    (net (code "68") (name "Net-(IC1A-D7)") (class "Default")
      (node (ref "IC1") (pin "17") (pinfunction "D7_17") (pintype "input"))
      (node (ref "V7") (pin "2") (pinfunction "QB_2") (pintype "output"))
    )
    (net (code "69") (name "Net-(IC1A-D8)") (class "Default")
      (node (ref "IC1") (pin "18") (pinfunction "D8_18") (pintype "input"))
      (node (ref "V7") (pin "3") (pinfunction "QA_3") (pintype "output"))
    )
    (net (code "70") (name "Net-(IC1A-Q1)") (class "Default")
      (node (ref "IC1") (pin "2") (pinfunction "Q1_2") (pintype "output"))
      (node (ref "IC4") (pin "2") (pinfunction "A1_2") (pintype "bidirectional"))
      (node (ref "IC6") (pin "2") (pinfunction "A1_2") (pintype "bidirectional"))
      (node (ref "LED_16") (pin "A") (pinfunction "A_A") (pintype "passive"))
    )
    (net (code "71") (name "Net-(IC1A-Q2)") (class "Default")
      (node (ref "IC1") (pin "5") (pinfunction "Q2_5") (pintype "output"))
      (node (ref "IC4") (pin "3") (pinfunction "A2_3") (pintype "bidirectional"))
      (node (ref "IC6") (pin "3") (pinfunction "A2_3") (pintype "bidirectional"))
      (node (ref "LED_15") (pin "A") (pinfunction "A_A") (pintype "passive"))
    )
    (net (code "72") (name "Net-(IC1A-Q3)") (class "Default")
      (node (ref "IC1") (pin "6") (pinfunction "Q3_6") (pintype "output"))
      (node (ref "IC4") (pin "4") (pinfunction "A3_4") (pintype "bidirectional"))
      (node (ref "IC6") (pin "4") (pinfunction "A3_4") (pintype "bidirectional"))
      (node (ref "LED_14") (pin "A") (pinfunction "A_A") (pintype "passive"))
    )
    (net (code "73") (name "Net-(IC1A-Q4)") (class "Default")
      (node (ref "IC1") (pin "9") (pinfunction "Q4_9") (pintype "output"))
      (node (ref "IC4") (pin "5") (pinfunction "A4_5") (pintype "bidirectional"))
      (node (ref "IC6") (pin "5") (pinfunction "A4_5") (pintype "bidirectional"))
      (node (ref "LED_13") (pin "A") (pinfunction "A_A") (pintype "passive"))
    )
    (net (code "74") (name "Net-(IC1A-Q5)") (class "Default")
      (node (ref "IC1") (pin "12") (pinfunction "Q5_12") (pintype "output"))
      (node (ref "IC4") (pin "6") (pinfunction "A5_6") (pintype "bidirectional"))
      (node (ref "IC6") (pin "6") (pinfunction "A5_6") (pintype "bidirectional"))
      (node (ref "LED_12") (pin "A") (pinfunction "A_A") (pintype "passive"))
    )
    (net (code "75") (name "Net-(IC1A-Q6)") (class "Default")
      (node (ref "IC1") (pin "15") (pinfunction "Q6_15") (pintype "output"))
      (node (ref "IC4") (pin "7") (pinfunction "A6_7") (pintype "bidirectional"))
      (node (ref "IC6") (pin "7") (pinfunction "A6_7") (pintype "bidirectional"))
      (node (ref "LED_11") (pin "A") (pinfunction "A_A") (pintype "passive"))
    )
    (net (code "76") (name "Net-(IC1A-Q7)") (class "Default")
      (node (ref "IC1") (pin "16") (pinfunction "Q7_16") (pintype "output"))
      (node (ref "IC4") (pin "8") (pinfunction "A7_8") (pintype "bidirectional"))
      (node (ref "IC6") (pin "8") (pinfunction "A7_8") (pintype "bidirectional"))
      (node (ref "LED_10") (pin "A") (pinfunction "A_A") (pintype "passive"))
    )
    (net (code "77") (name "Net-(IC1A-Q8)") (class "Default")
      (node (ref "IC1") (pin "19") (pinfunction "Q8_19") (pintype "output"))
      (node (ref "IC4") (pin "9") (pinfunction "A8_9") (pintype "bidirectional"))
      (node (ref "IC6") (pin "9") (pinfunction "A8_9") (pintype "bidirectional"))
      (node (ref "LED_9") (pin "A") (pinfunction "A_A") (pintype "passive"))
    )
    (net (code "78") (name "Net-(IC2A-D1)") (class "Default")
      (node (ref "IC2") (pin "3") (pinfunction "D1_3") (pintype "input"))
      (node (ref "V6") (pin "7") (pinfunction "QD_7") (pintype "output"))
    )
    (net (code "79") (name "Net-(IC2A-D2)") (class "Default")
      (node (ref "IC2") (pin "4") (pinfunction "D2_4") (pintype "input"))
      (node (ref "V6") (pin "6") (pinfunction "QC_6") (pintype "output"))
    )
    (net (code "80") (name "Net-(IC2A-D3)") (class "Default")
      (node (ref "IC2") (pin "7") (pinfunction "D3_7") (pintype "input"))
      (node (ref "V6") (pin "2") (pinfunction "QB_2") (pintype "output"))
    )
    (net (code "81") (name "Net-(IC2A-D4)") (class "Default")
      (node (ref "IC2") (pin "8") (pinfunction "D4_8") (pintype "input"))
      (node (ref "V6") (pin "3") (pinfunction "QA_3") (pintype "output"))
    )
    (net (code "82") (name "Net-(IC2A-D5)") (class "Default")
      (node (ref "IC2") (pin "13") (pinfunction "D5_13") (pintype "input"))
      (node (ref "V5") (pin "7") (pinfunction "QD_7") (pintype "output"))
    )
    (net (code "83") (name "Net-(IC2A-D6)") (class "Default")
      (node (ref "IC2") (pin "14") (pinfunction "D6_14") (pintype "input"))
      (node (ref "V5") (pin "6") (pinfunction "QC_6") (pintype "output"))
    )
    (net (code "84") (name "Net-(IC2A-D7)") (class "Default")
      (node (ref "IC2") (pin "17") (pinfunction "D7_17") (pintype "input"))
      (node (ref "V5") (pin "2") (pinfunction "QB_2") (pintype "output"))
    )
    (net (code "85") (name "Net-(IC2A-D8)") (class "Default")
      (node (ref "IC2") (pin "18") (pinfunction "D8_18") (pintype "input"))
      (node (ref "V5") (pin "3") (pinfunction "QA_3") (pintype "output"))
    )
    (net (code "86") (name "Net-(IC2A-Q1)") (class "Default")
      (node (ref "IC2") (pin "2") (pinfunction "Q1_2") (pintype "output"))
      (node (ref "IC3") (pin "2") (pinfunction "A1_2") (pintype "bidirectional"))
      (node (ref "IC5") (pin "2") (pinfunction "A1_2") (pintype "bidirectional"))
      (node (ref "LED_8") (pin "A") (pinfunction "A_A") (pintype "passive"))
    )
    (net (code "87") (name "Net-(IC2A-Q2)") (class "Default")
      (node (ref "IC2") (pin "5") (pinfunction "Q2_5") (pintype "output"))
      (node (ref "IC3") (pin "3") (pinfunction "A2_3") (pintype "bidirectional"))
      (node (ref "IC5") (pin "3") (pinfunction "A2_3") (pintype "bidirectional"))
      (node (ref "LED_7") (pin "A") (pinfunction "A_A") (pintype "passive"))
    )
    (net (code "88") (name "Net-(IC2A-Q3)") (class "Default")
      (node (ref "IC2") (pin "6") (pinfunction "Q3_6") (pintype "output"))
      (node (ref "IC3") (pin "4") (pinfunction "A3_4") (pintype "bidirectional"))
      (node (ref "IC5") (pin "4") (pinfunction "A3_4") (pintype "bidirectional"))
      (node (ref "LED_6") (pin "A") (pinfunction "A_A") (pintype "passive"))
    )
    (net (code "89") (name "Net-(IC2A-Q4)") (class "Default")
      (node (ref "IC2") (pin "9") (pinfunction "Q4_9") (pintype "output"))
      (node (ref "IC3") (pin "5") (pinfunction "A4_5") (pintype "bidirectional"))
      (node (ref "IC5") (pin "5") (pinfunction "A4_5") (pintype "bidirectional"))
      (node (ref "LED_5") (pin "A") (pinfunction "A_A") (pintype "passive"))
    )
    (net (code "90") (name "Net-(IC2A-Q5)") (class "Default")
      (node (ref "IC2") (pin "12") (pinfunction "Q5_12") (pintype "output"))
      (node (ref "IC3") (pin "6") (pinfunction "A5_6") (pintype "bidirectional"))
      (node (ref "IC5") (pin "6") (pinfunction "A5_6") (pintype "bidirectional"))
      (node (ref "LED_4") (pin "A") (pinfunction "A_A") (pintype "passive"))
    )
    (net (code "91") (name "Net-(IC2A-Q6)") (class "Default")
      (node (ref "IC2") (pin "15") (pinfunction "Q6_15") (pintype "output"))
      (node (ref "IC3") (pin "7") (pinfunction "A6_7") (pintype "bidirectional"))
      (node (ref "IC5") (pin "7") (pinfunction "A6_7") (pintype "bidirectional"))
      (node (ref "LED_3") (pin "A") (pinfunction "A_A") (pintype "passive"))
    )
    (net (code "92") (name "Net-(IC2A-Q7)") (class "Default")
      (node (ref "IC2") (pin "16") (pinfunction "Q7_16") (pintype "output"))
      (node (ref "IC3") (pin "8") (pinfunction "A7_8") (pintype "bidirectional"))
      (node (ref "IC5") (pin "8") (pinfunction "A7_8") (pintype "bidirectional"))
      (node (ref "LED_2") (pin "A") (pinfunction "A_A") (pintype "passive"))
    )
    (net (code "93") (name "Net-(IC2A-Q8)") (class "Default")
      (node (ref "IC2") (pin "19") (pinfunction "Q8_19") (pintype "output"))
      (node (ref "IC3") (pin "9") (pinfunction "A8_9") (pintype "bidirectional"))
      (node (ref "IC5") (pin "9") (pinfunction "A8_9") (pintype "bidirectional"))
      (node (ref "LED_1") (pin "A") (pinfunction "A_A") (pintype "passive"))
    )
    (net (code "94") (name "Net-(IC7A-O)") (class "Default")
      (node (ref "IC7") (pin "3") (pinfunction "O_3") (pintype "output"))
      (node (ref "V5") (pin "5") (pinfunction "UP_5") (pintype "input"))
    )
    (net (code "95") (name "Net-(IC7B-O)") (class "Default")
      (node (ref "IC7") (pin "6") (pinfunction "O_6") (pintype "output"))
      (node (ref "V5") (pin "4") (pinfunction "DOWN_4") (pintype "input"))
    )
    (net (code "96") (name "Net-(IC7C-O)") (class "Default")
      (node (ref "IC7") (pin "8") (pinfunction "O_8") (pintype "output"))
      (node (ref "V5") (pin "11") (pinfunction "~{LOAD}_11") (pintype "input"))
      (node (ref "V6") (pin "11") (pinfunction "~{LOAD}_11") (pintype "input"))
      (node (ref "V7") (pin "11") (pinfunction "~{LOAD}_11") (pintype "input"))
      (node (ref "V8") (pin "11") (pinfunction "~{LOAD}_11") (pintype "input"))
    )
    (net (code "97") (name "Net-(INC-A2)") (class "Default")
      (node (ref "INC") (pin "2") (pinfunction "A2_2") (pintype "passive"))
      (node (ref "R22") (pin "1") (pinfunction "1_1") (pintype "passive"))
    )
    (net (code "98") (name "Net-(LED_1-PadC)") (class "Default")
      (node (ref "LED_1") (pin "C") (pinfunction "C_C") (pintype "passive"))
      (node (ref "R1") (pin "2") (pinfunction "2_2") (pintype "passive"))
    )
    (net (code "99") (name "Net-(LED_2-PadC)") (class "Default")
      (node (ref "LED_2") (pin "C") (pinfunction "C_C") (pintype "passive"))
      (node (ref "R2") (pin "2") (pinfunction "2_2") (pintype "passive"))
    )
    (net (code "100") (name "Net-(LED_3-PadC)") (class "Default")
      (node (ref "LED_3") (pin "C") (pinfunction "C_C") (pintype "passive"))
      (node (ref "R3") (pin "2") (pinfunction "2_2") (pintype "passive"))
    )
    (net (code "101") (name "Net-(LED_4-PadC)") (class "Default")
      (node (ref "LED_4") (pin "C") (pinfunction "C_C") (pintype "passive"))
      (node (ref "R4") (pin "2") (pinfunction "2_2") (pintype "passive"))
    )
    (net (code "102") (name "Net-(LED_5-PadC)") (class "Default")
      (node (ref "LED_5") (pin "C") (pinfunction "C_C") (pintype "passive"))
      (node (ref "R5") (pin "2") (pinfunction "2_2") (pintype "passive"))
    )
    (net (code "103") (name "Net-(LED_6-PadC)") (class "Default")
      (node (ref "LED_6") (pin "C") (pinfunction "C_C") (pintype "passive"))
      (node (ref "R6") (pin "2") (pinfunction "2_2") (pintype "passive"))
    )
    (net (code "104") (name "Net-(LED_7-PadC)") (class "Default")
      (node (ref "LED_7") (pin "C") (pinfunction "C_C") (pintype "passive"))
      (node (ref "R7") (pin "2") (pinfunction "2_2") (pintype "passive"))
    )
    (net (code "105") (name "Net-(LED_8-PadC)") (class "Default")
      (node (ref "LED_8") (pin "C") (pinfunction "C_C") (pintype "passive"))
      (node (ref "R8") (pin "2") (pinfunction "2_2") (pintype "passive"))
    )
    (net (code "106") (name "Net-(LED_9-PadC)") (class "Default")
      (node (ref "LED_9") (pin "C") (pinfunction "C_C") (pintype "passive"))
      (node (ref "R9") (pin "2") (pinfunction "2_2") (pintype "passive"))
    )
    (net (code "107") (name "Net-(LED_10-PadC)") (class "Default")
      (node (ref "LED_10") (pin "C") (pinfunction "C_C") (pintype "passive"))
      (node (ref "R10") (pin "2") (pinfunction "2_2") (pintype "passive"))
    )
    (net (code "108") (name "Net-(LED_11-PadC)") (class "Default")
      (node (ref "LED_11") (pin "C") (pinfunction "C_C") (pintype "passive"))
      (node (ref "R11") (pin "2") (pinfunction "2_2") (pintype "passive"))
    )
    (net (code "109") (name "Net-(LED_12-PadC)") (class "Default")
      (node (ref "LED_12") (pin "C") (pinfunction "C_C") (pintype "passive"))
      (node (ref "R12") (pin "2") (pinfunction "2_2") (pintype "passive"))
    )
    (net (code "110") (name "Net-(LED_13-PadC)") (class "Default")
      (node (ref "LED_13") (pin "C") (pinfunction "C_C") (pintype "passive"))
      (node (ref "R13") (pin "2") (pinfunction "2_2") (pintype "passive"))
    )
    (net (code "111") (name "Net-(LED_14-PadC)") (class "Default")
      (node (ref "LED_14") (pin "C") (pinfunction "C_C") (pintype "passive"))
      (node (ref "R14") (pin "2") (pinfunction "2_2") (pintype "passive"))
    )
    (net (code "112") (name "Net-(LED_15-PadC)") (class "Default")
      (node (ref "LED_15") (pin "C") (pinfunction "C_C") (pintype "passive"))
      (node (ref "R15") (pin "2") (pinfunction "2_2") (pintype "passive"))
    )
    (net (code "113") (name "Net-(LED_16-PadC)") (class "Default")
      (node (ref "LED_16") (pin "C") (pinfunction "C_C") (pintype "passive"))
      (node (ref "R16") (pin "2") (pinfunction "2_2") (pintype "passive"))
    )
    (net (code "114") (name "Net-(LOAD-A2)") (class "Default")
      (node (ref "LOAD") (pin "2") (pinfunction "A2_2") (pintype "passive"))
      (node (ref "R21") (pin "1") (pinfunction "1_1") (pintype "passive"))
    )
    (net (code "115") (name "Net-(RESET-K2)") (class "Default")
      (node (ref "R18") (pin "2") (pinfunction "2_2") (pintype "passive"))
      (node (ref "RESET") (pin "1") (pinfunction "K2_1") (pintype "passive"))
    )
    (net (code "116") (name "Net-(V5C-~{BO})") (class "Default")
      (node (ref "V5") (pin "13") (pinfunction "~{BO}_13") (pintype "output"))
      (node (ref "V6") (pin "4") (pinfunction "DOWN_4") (pintype "input"))
    )
    (net (code "117") (name "Net-(V5C-~{CO})") (class "Default")
      (node (ref "V5") (pin "12") (pinfunction "~{CO}_12") (pintype "output"))
      (node (ref "V6") (pin "5") (pinfunction "UP_5") (pintype "input"))
    )
    (net (code "118") (name "Net-(V6C-~{BO})") (class "Default")
      (node (ref "V6") (pin "13") (pinfunction "~{BO}_13") (pintype "output"))
      (node (ref "V7") (pin "4") (pinfunction "DOWN_4") (pintype "input"))
    )
    (net (code "119") (name "Net-(V6C-~{CO})") (class "Default")
      (node (ref "V6") (pin "12") (pinfunction "~{CO}_12") (pintype "output"))
      (node (ref "V7") (pin "5") (pinfunction "UP_5") (pintype "input"))
    )
    (net (code "120") (name "Net-(V7C-~{BO})") (class "Default")
      (node (ref "V7") (pin "13") (pinfunction "~{BO}_13") (pintype "output"))
      (node (ref "V8") (pin "4") (pinfunction "DOWN_4") (pintype "input"))
    )
    (net (code "121") (name "Net-(V7C-~{CO})") (class "Default")
      (node (ref "V7") (pin "12") (pinfunction "~{CO}_12") (pintype "output"))
      (node (ref "V8") (pin "5") (pinfunction "UP_5") (pintype "input"))
    )
    (net (code "122") (name "VCC") (class "Default")
      (node (ref "C1") (pin "1") (pinfunction "1_1") (pintype "passive"))
      (node (ref "C10") (pin "1") (pinfunction "1_1") (pintype "passive"))
      (node (ref "C11") (pin "1") (pinfunction "1_1") (pintype "passive"))
      (node (ref "C12") (pin "1") (pinfunction "1_1") (pintype "passive"))
      (node (ref "C14") (pin "1") (pinfunction "1_1") (pintype "passive"))
      (node (ref "C15") (pin "1") (pinfunction "1_1") (pintype "passive"))
      (node (ref "C16") (pin "1") (pinfunction "1_1") (pintype "passive"))
      (node (ref "C2") (pin "1") (pinfunction "1_1") (pintype "passive"))
      (node (ref "C3") (pin "1") (pinfunction "1_1") (pintype "passive"))
      (node (ref "C4") (pin "1") (pinfunction "1_1") (pintype "passive"))
      (node (ref "C5") (pin "1") (pinfunction "1_1") (pintype "passive"))
      (node (ref "C6") (pin "1") (pinfunction "1_1") (pintype "passive"))
      (node (ref "C7") (pin "1") (pinfunction "1_1") (pintype "passive"))
      (node (ref "C8") (pin "1") (pinfunction "1_1") (pintype "passive"))
      (node (ref "C9") (pin "1") (pinfunction "1_1") (pintype "passive"))
      (node (ref "IC1") (pin "20") (pinfunction "VCC_20") (pintype "power_in"))
      (node (ref "IC2") (pin "20") (pinfunction "VCC_20") (pintype "power_in"))
      (node (ref "IC3") (pin "1") (pinfunction "DIR_1") (pintype "input"))
      (node (ref "IC3") (pin "20") (pinfunction "VCC_20") (pintype "power_in"))
      (node (ref "IC4") (pin "1") (pinfunction "DIR_1") (pintype "input"))
      (node (ref "IC4") (pin "20") (pinfunction "VCC_20") (pintype "power_in"))
      (node (ref "IC5") (pin "1") (pinfunction "DIR_1") (pintype "input"))
      (node (ref "IC5") (pin "20") (pinfunction "VCC_20") (pintype "power_in"))
      (node (ref "IC6") (pin "1") (pinfunction "DIR_1") (pintype "input"))
      (node (ref "IC6") (pin "20") (pinfunction "VCC_20") (pintype "power_in"))
      (node (ref "IC7") (pin "12") (pinfunction "I0_12") (pintype "input"))
      (node (ref "IC7") (pin "13") (pinfunction "I1_13") (pintype "input"))
      (node (ref "IC7") (pin "14") (pinfunction "VCC_14") (pintype "power_in"))
      (node (ref "R19") (pin "2") (pinfunction "2_2") (pintype "passive"))
      (node (ref "R20") (pin "2") (pinfunction "2_2") (pintype "passive"))
      (node (ref "R21") (pin "2") (pinfunction "2_2") (pintype "passive"))
      (node (ref "R22") (pin "2") (pinfunction "2_2") (pintype "passive"))
      (node (ref "R23") (pin "2") (pinfunction "2_2") (pintype "passive"))
      (node (ref "SV_CREG_1") (pin "1") (pinfunction "1_1") (pintype "passive"))
      (node (ref "SV_CREG_1") (pin "36") (pinfunction "36_36") (pintype "passive"))
      (node (ref "SV_CREG_2") (pin "1") (pinfunction "1_1") (pintype "passive"))
      (node (ref "SV_CREG_2") (pin "36") (pinfunction "36_36") (pintype "passive"))
      (node (ref "V5") (pin "16") (pinfunction "+UB_16") (pintype "power_in"))
      (node (ref "V6") (pin "16") (pinfunction "+UB_16") (pintype "power_in"))
      (node (ref "V7") (pin "16") (pinfunction "+UB_16") (pintype "power_in"))
      (node (ref "V8") (pin "16") (pinfunction "+UB_16") (pintype "power_in"))
    )
    (net (code "123") (name "unconnected-(IC7D-O-Pad11)") (class "Default")
      (node (ref "IC7") (pin "11") (pinfunction "O_11") (pintype "output"))
    )
    (net (code "124") (name "unconnected-(SV_CREG_1-Pad4)") (class "Default")
      (node (ref "SV_CREG_1") (pin "4") (pinfunction "4_4") (pintype "passive"))
    )
    (net (code "125") (name "unconnected-(SV_CREG_1-Pad6)") (class "Default")
      (node (ref "SV_CREG_1") (pin "6") (pinfunction "6_6") (pintype "passive"))
    )
    (net (code "126") (name "unconnected-(SV_CREG_1-Pad8)") (class "Default")
      (node (ref "SV_CREG_1") (pin "8") (pinfunction "8_8") (pintype "passive"))
    )
    (net (code "127") (name "unconnected-(SV_CREG_1-Pad10)") (class "Default")
      (node (ref "SV_CREG_1") (pin "10") (pinfunction "10_10") (pintype "passive"))
    )
    (net (code "128") (name "unconnected-(SV_CREG_1-Pad12)") (class "Default")
      (node (ref "SV_CREG_1") (pin "12") (pinfunction "12_12") (pintype "passive"))
    )
    (net (code "129") (name "unconnected-(SV_CREG_1-Pad14)") (class "Default")
      (node (ref "SV_CREG_1") (pin "14") (pinfunction "14_14") (pintype "passive"))
    )
    (net (code "130") (name "unconnected-(SV_CREG_1-Pad15)") (class "Default")
      (node (ref "SV_CREG_1") (pin "15") (pinfunction "15_15") (pintype "passive"))
    )
    (net (code "131") (name "unconnected-(SV_CREG_1-Pad17)") (class "Default")
      (node (ref "SV_CREG_1") (pin "17") (pinfunction "17_17") (pintype "passive"))
    )
    (net (code "132") (name "unconnected-(SV_CREG_1-Pad19)") (class "Default")
      (node (ref "SV_CREG_1") (pin "19") (pinfunction "19_19") (pintype "passive"))
    )
    (net (code "133") (name "unconnected-(SV_CREG_1-Pad21)") (class "Default")
      (node (ref "SV_CREG_1") (pin "21") (pinfunction "21_21") (pintype "passive"))
    )
    (net (code "134") (name "unconnected-(SV_CREG_1-Pad23)") (class "Default")
      (node (ref "SV_CREG_1") (pin "23") (pinfunction "23_23") (pintype "passive"))
    )
    (net (code "135") (name "unconnected-(SV_CREG_1-Pad25)") (class "Default")
      (node (ref "SV_CREG_1") (pin "25") (pinfunction "25_25") (pintype "passive"))
    )
    (net (code "136") (name "unconnected-(SV_CREG_1-Pad27)") (class "Default")
      (node (ref "SV_CREG_1") (pin "27") (pinfunction "27_27") (pintype "passive"))
    )
    (net (code "137") (name "unconnected-(V8C-~{BO}-Pad13)") (class "Default")
      (node (ref "V8") (pin "13") (pinfunction "~{BO}_13") (pintype "output"))
    )
    (net (code "138") (name "unconnected-(V8C-~{CO}-Pad12)") (class "Default")
      (node (ref "V8") (pin "12") (pinfunction "~{CO}_12") (pintype "output"))
    )
  )
)
